# HW2_circuit.net
KiCad netlist of a schematic drawn in EAGLE
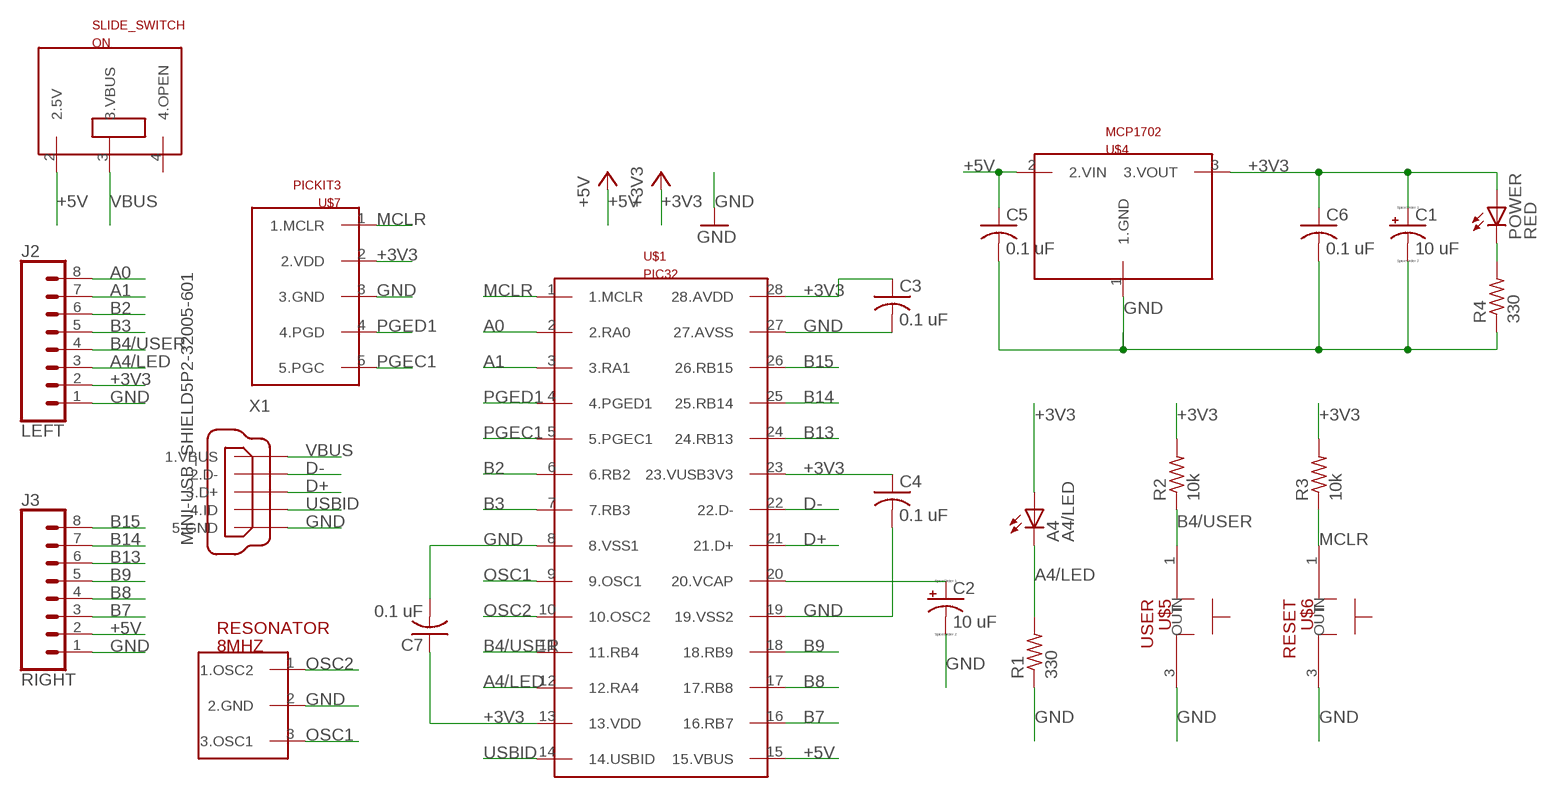
[diagram p0: schematic, sheet 1]

(export (version "E")
  (design (tool "Eeschema 10.0.6"))
  (components
    (comp (ref "8MHZ")
      (value "RESONATOR")
      (footprint "eagle-import:OSCILLATOR")
      (libsource (lib "eagle-import") (part "RESONATOR"))
    )
    (comp (ref "A4")
      (value "A4/LED")
      (footprint "eagle-import:LED3MM")
      (libsource (lib "eagle-import") (part "LED3MM"))
    )
    (comp (ref "C1")
      (value "10 uF")
      (footprint "eagle-import:B45181B")
      (libsource (lib "eagle-import") (part "CPOL-USB45181B"))
    )
    (comp (ref "C2")
      (value "10 uF")
      (footprint "eagle-import:B45181B")
      (libsource (lib "eagle-import") (part "CPOL-USB45181B"))
    )
    (comp (ref "C3")
      (value "0.1 uF")
      (footprint "eagle-import:C025-025X050")
      (libsource (lib "eagle-import") (part "C-US025-025X050"))
    )
    (comp (ref "C4")
      (value "0.1 uF")
      (footprint "eagle-import:C025-025X050")
      (libsource (lib "eagle-import") (part "C-US025-025X050"))
    )
    (comp (ref "C5")
      (value "0.1 uF")
      (footprint "eagle-import:C025-025X050")
      (libsource (lib "eagle-import") (part "C-US025-025X050"))
    )
    (comp (ref "C6")
      (value "0.1 uF")
      (footprint "eagle-import:C025-025X050")
      (libsource (lib "eagle-import") (part "C-US025-025X050"))
    )
    (comp (ref "C7")
      (value "0.1 uF")
      (footprint "eagle-import:C025-025X050")
      (libsource (lib "eagle-import") (part "C-US025-025X050"))
    )
    (comp (ref "J2")
      (value "LEFT")
      (footprint "eagle-import:1X08")
      (libsource (lib "eagle-import") (part "CONN_08{dblquote}"))
    )
    (comp (ref "J3")
      (value "RIGHT")
      (footprint "eagle-import:1X08")
      (libsource (lib "eagle-import") (part "CONN_08{dblquote}"))
    )
    (comp (ref "ON")
      (value "SLIDE_SWITCH")
      (footprint "eagle-import:SLIDE_SWITCH")
      (libsource (lib "eagle-import") (part "SLIDE_SWITCH"))
    )
    (comp (ref "POWER")
      (value "RED")
      (footprint "eagle-import:LED3MM")
      (libsource (lib "eagle-import") (part "LED3MM"))
    )
    (comp (ref "R1")
      (value "330")
      (footprint "eagle-import:0207_10")
      (libsource (lib "eagle-import") (part "R-US_0207/10"))
    )
    (comp (ref "R2")
      (value "10k")
      (footprint "eagle-import:0207_10")
      (libsource (lib "eagle-import") (part "R-US_0207/10"))
    )
    (comp (ref "R3")
      (value "10k")
      (footprint "eagle-import:0207_10")
      (libsource (lib "eagle-import") (part "R-US_0207/10"))
    )
    (comp (ref "R4")
      (value "330")
      (footprint "eagle-import:0207_10")
      (libsource (lib "eagle-import") (part "R-US_0207/10"))
    )
    (comp (ref "U$1")
      (value "PIC32")
      (footprint "eagle-import:DIL28-3")
      (libsource (lib "eagle-import") (part "PIC32MX250F128B"))
    )
    (comp (ref "U$4")
      (value "MCP1702")
      (footprint "eagle-import:TO92")
      (libsource (lib "eagle-import") (part "MCP1702"))
    )
    (comp (ref "U$5")
      (value "USER")
      (footprint "eagle-import:BUTTON")
      (libsource (lib "eagle-import") (part "BUTTON"))
    )
    (comp (ref "U$6")
      (value "RESET")
      (footprint "eagle-import:BUTTON")
      (libsource (lib "eagle-import") (part "BUTTON"))
    )
    (comp (ref "U$7")
      (value "PICKIT3")
      (footprint "eagle-import:PICKIT32")
      (libsource (lib "eagle-import") (part "PICKIT32"))
    )
    (comp (ref "X1")
      (value "MINI-USB_SHIELD5P2-32005-601")
      (footprint "eagle-import:32005-601")
      (libsource (lib "eagle-import") (part "MINI-USB_SHIELD5P2-32005-601"))
    )
  )
  (nets
    (net (code "1") (name "+3V3") (class "Default")
      (node (ref "A4") (pin "A") (pinfunction "A_A") (pintype "passive"))
      (node (ref "C1") (pin "+") (pinfunction "+_+") (pintype "passive"))
      (node (ref "C3") (pin "1") (pinfunction "1_1") (pintype "passive"))
      (node (ref "C4") (pin "1") (pinfunction "1_1") (pintype "passive"))
      (node (ref "C6") (pin "1") (pinfunction "1_1") (pintype "passive"))
      (node (ref "C7") (pin "1") (pinfunction "1_1") (pintype "passive"))
      (node (ref "J2") (pin "2") (pinfunction "2_2") (pintype "passive"))
      (node (ref "POWER") (pin "A") (pinfunction "A_A") (pintype "passive"))
      (node (ref "R2") (pin "2") (pinfunction "2_2") (pintype "passive"))
      (node (ref "R3") (pin "2") (pinfunction "2_2") (pintype "passive"))
      (node (ref "U$1") (pin "13") (pinfunction "13.VDD_13") (pintype "bidirectional"))
      (node (ref "U$1") (pin "23") (pinfunction "23.VUSB3V3_23") (pintype "bidirectional"))
      (node (ref "U$1") (pin "28") (pinfunction "28.AVDD_28") (pintype "bidirectional"))
      (node (ref "U$4") (pin "3") (pinfunction "3.VOUT_3") (pintype "bidirectional"))
      (node (ref "U$7") (pin "2") (pinfunction "2.VDD_2") (pintype "bidirectional"))
    )
    (net (code "2") (name "+5V") (class "Default")
      (node (ref "C5") (pin "1") (pinfunction "1_1") (pintype "passive"))
      (node (ref "J3") (pin "2") (pinfunction "2_2") (pintype "passive"))
      (node (ref "ON") (pin "2") (pinfunction "2.5V_2") (pintype "bidirectional"))
      (node (ref "U$1") (pin "15") (pinfunction "15.VBUS_15") (pintype "bidirectional"))
      (node (ref "U$4") (pin "2") (pinfunction "2.VIN_2") (pintype "bidirectional"))
    )
    (net (code "3") (name "/A0") (class "Default")
      (node (ref "J2") (pin "8") (pinfunction "8_8") (pintype "passive"))
      (node (ref "U$1") (pin "2") (pinfunction "2.RA0_2") (pintype "bidirectional"))
    )
    (net (code "4") (name "/A1") (class "Default")
      (node (ref "J2") (pin "7") (pinfunction "7_7") (pintype "passive"))
      (node (ref "U$1") (pin "3") (pinfunction "3.RA1_3") (pintype "bidirectional"))
    )
    (net (code "5") (name "/A4{slash}LED") (class "Default")
      (node (ref "A4") (pin "K") (pinfunction "C_K") (pintype "passive"))
      (node (ref "J2") (pin "3") (pinfunction "3_3") (pintype "passive"))
      (node (ref "R1") (pin "2") (pinfunction "2_2") (pintype "passive"))
      (node (ref "U$1") (pin "12") (pinfunction "12.RA4_12") (pintype "bidirectional"))
    )
    (net (code "6") (name "/B2") (class "Default")
      (node (ref "J2") (pin "6") (pinfunction "6_6") (pintype "passive"))
      (node (ref "U$1") (pin "6") (pinfunction "6.RB2_6") (pintype "bidirectional"))
    )
    (net (code "7") (name "/B3") (class "Default")
      (node (ref "J2") (pin "5") (pinfunction "5_5") (pintype "passive"))
      (node (ref "U$1") (pin "7") (pinfunction "7.RB3_7") (pintype "bidirectional"))
    )
    (net (code "8") (name "/B4{slash}USER") (class "Default")
      (node (ref "J2") (pin "4") (pinfunction "4_4") (pintype "passive"))
      (node (ref "R2") (pin "1") (pinfunction "1_1") (pintype "passive"))
      (node (ref "U$1") (pin "11") (pinfunction "11.RB4_11") (pintype "bidirectional"))
      (node (ref "U$5") (pin "1") (pinfunction "IN_1") (pintype "bidirectional"))
    )
    (net (code "9") (name "/B7") (class "Default")
      (node (ref "J3") (pin "3") (pinfunction "3_3") (pintype "passive"))
      (node (ref "U$1") (pin "16") (pinfunction "16.RB7_16") (pintype "bidirectional"))
    )
    (net (code "10") (name "/B8") (class "Default")
      (node (ref "J3") (pin "4") (pinfunction "4_4") (pintype "passive"))
      (node (ref "U$1") (pin "17") (pinfunction "17.RB8_17") (pintype "bidirectional"))
    )
    (net (code "11") (name "/B9") (class "Default")
      (node (ref "J3") (pin "5") (pinfunction "5_5") (pintype "passive"))
      (node (ref "U$1") (pin "18") (pinfunction "18.RB9_18") (pintype "bidirectional"))
    )
    (net (code "12") (name "/B13") (class "Default")
      (node (ref "J3") (pin "6") (pinfunction "6_6") (pintype "passive"))
      (node (ref "U$1") (pin "24") (pinfunction "24.RB13_24") (pintype "bidirectional"))
    )
    (net (code "13") (name "/B14") (class "Default")
      (node (ref "J3") (pin "7") (pinfunction "7_7") (pintype "passive"))
      (node (ref "U$1") (pin "25") (pinfunction "25.RB14_25") (pintype "bidirectional"))
    )
    (net (code "14") (name "/B15") (class "Default")
      (node (ref "J3") (pin "8") (pinfunction "8_8") (pintype "passive"))
      (node (ref "U$1") (pin "26") (pinfunction "26.RB15_26") (pintype "bidirectional"))
    )
    (net (code "15") (name "/D+") (class "Default")
      (node (ref "U$1") (pin "21") (pinfunction "21.D+_21") (pintype "bidirectional"))
      (node (ref "X1") (pin "3") (pinfunction "3.D+_3") (pintype "passive"))
    )
    (net (code "16") (name "/D-") (class "Default")
      (node (ref "U$1") (pin "22") (pinfunction "22.D-_22") (pintype "bidirectional"))
      (node (ref "X1") (pin "2") (pinfunction "2.D-_2") (pintype "passive"))
    )
    (net (code "17") (name "/MCLR") (class "Default")
      (node (ref "R3") (pin "1") (pinfunction "1_1") (pintype "passive"))
      (node (ref "U$1") (pin "1") (pinfunction "1.MCLR_1") (pintype "bidirectional"))
      (node (ref "U$6") (pin "1") (pinfunction "IN_1") (pintype "bidirectional"))
      (node (ref "U$7") (pin "1") (pinfunction "1.MCLR_1") (pintype "bidirectional"))
    )
    (net (code "18") (name "/OSC1") (class "Default")
      (node (ref "8MHZ") (pin "3") (pinfunction "3.OSC1_3") (pintype "bidirectional"))
      (node (ref "U$1") (pin "9") (pinfunction "9.OSC1_9") (pintype "bidirectional"))
    )
    (net (code "19") (name "/OSC2") (class "Default")
      (node (ref "8MHZ") (pin "1") (pinfunction "1.OSC2_1") (pintype "bidirectional"))
      (node (ref "U$1") (pin "10") (pinfunction "10.OSC2_10") (pintype "bidirectional"))
    )
    (net (code "20") (name "/PGEC1") (class "Default")
      (node (ref "U$1") (pin "5") (pinfunction "5.PGEC1_5") (pintype "bidirectional"))
      (node (ref "U$7") (pin "5") (pinfunction "5.PGC_5") (pintype "bidirectional"))
    )
    (net (code "21") (name "/PGED1") (class "Default")
      (node (ref "U$1") (pin "4") (pinfunction "4.PGED1_4") (pintype "bidirectional"))
      (node (ref "U$7") (pin "4") (pinfunction "4.PGD_4") (pintype "bidirectional"))
    )
    (net (code "22") (name "/USBID") (class "Default")
      (node (ref "U$1") (pin "14") (pinfunction "14.USBID_14") (pintype "bidirectional"))
      (node (ref "X1") (pin "4") (pinfunction "4.ID_4") (pintype "passive"))
    )
    (net (code "23") (name "/VBUS") (class "Default")
      (node (ref "ON") (pin "3") (pinfunction "3.VBUS_3") (pintype "bidirectional"))
      (node (ref "X1") (pin "1") (pinfunction "1.VBUS_1") (pintype "passive"))
    )
    (net (code "24") (name "GND") (class "Default")
      (node (ref "8MHZ") (pin "2") (pinfunction "2.GND_2") (pintype "bidirectional"))
      (node (ref "C1") (pin "-") (pinfunction "-_-") (pintype "passive"))
      (node (ref "C2") (pin "-") (pinfunction "-_-") (pintype "passive"))
      (node (ref "C3") (pin "2") (pinfunction "2_2") (pintype "passive"))
      (node (ref "C4") (pin "2") (pinfunction "2_2") (pintype "passive"))
      (node (ref "C5") (pin "2") (pinfunction "2_2") (pintype "passive"))
      (node (ref "C6") (pin "2") (pinfunction "2_2") (pintype "passive"))
      (node (ref "C7") (pin "2") (pinfunction "2_2") (pintype "passive"))
      (node (ref "J2") (pin "1") (pinfunction "1_1") (pintype "passive"))
      (node (ref "J3") (pin "1") (pinfunction "1_1") (pintype "passive"))
      (node (ref "R1") (pin "1") (pinfunction "1_1") (pintype "passive"))
      (node (ref "R4") (pin "1") (pinfunction "1_1") (pintype "passive"))
      (node (ref "U$1") (pin "19") (pinfunction "19.VSS2_19") (pintype "bidirectional"))
      (node (ref "U$1") (pin "27") (pinfunction "27.AVSS_27") (pintype "bidirectional"))
      (node (ref "U$1") (pin "8") (pinfunction "8.VSS1_8") (pintype "bidirectional"))
      (node (ref "U$4") (pin "1") (pinfunction "1.GND_1") (pintype "bidirectional"))
      (node (ref "U$5") (pin "3") (pinfunction "OUT_3") (pintype "bidirectional"))
      (node (ref "U$6") (pin "3") (pinfunction "OUT_3") (pintype "bidirectional"))
      (node (ref "U$7") (pin "3") (pinfunction "3.GND_3") (pintype "bidirectional"))
      (node (ref "X1") (pin "5") (pinfunction "5.GND_5") (pintype "passive"))
    )
    (net (code "25") (name "Net-(POWER-C)") (class "Default")
      (node (ref "POWER") (pin "K") (pinfunction "C_K") (pintype "passive"))
      (node (ref "R4") (pin "2") (pinfunction "2_2") (pintype "passive"))
    )
    (net (code "26") (name "Net-(U$1-20.VCAP)") (class "Default")
      (node (ref "C2") (pin "+") (pinfunction "+_+") (pintype "passive"))
      (node (ref "U$1") (pin "20") (pinfunction "20.VCAP_20") (pintype "bidirectional"))
    )
    (net (code "27") (name "unconnected-(ON-4.OPEN-Pad4)") (class "Default")
      (node (ref "ON") (pin "4") (pinfunction "4.OPEN_4") (pintype "bidirectional"))
    )
  )
)
